# reflow.net
KiCad netlist of a schematic drawn in EAGLE
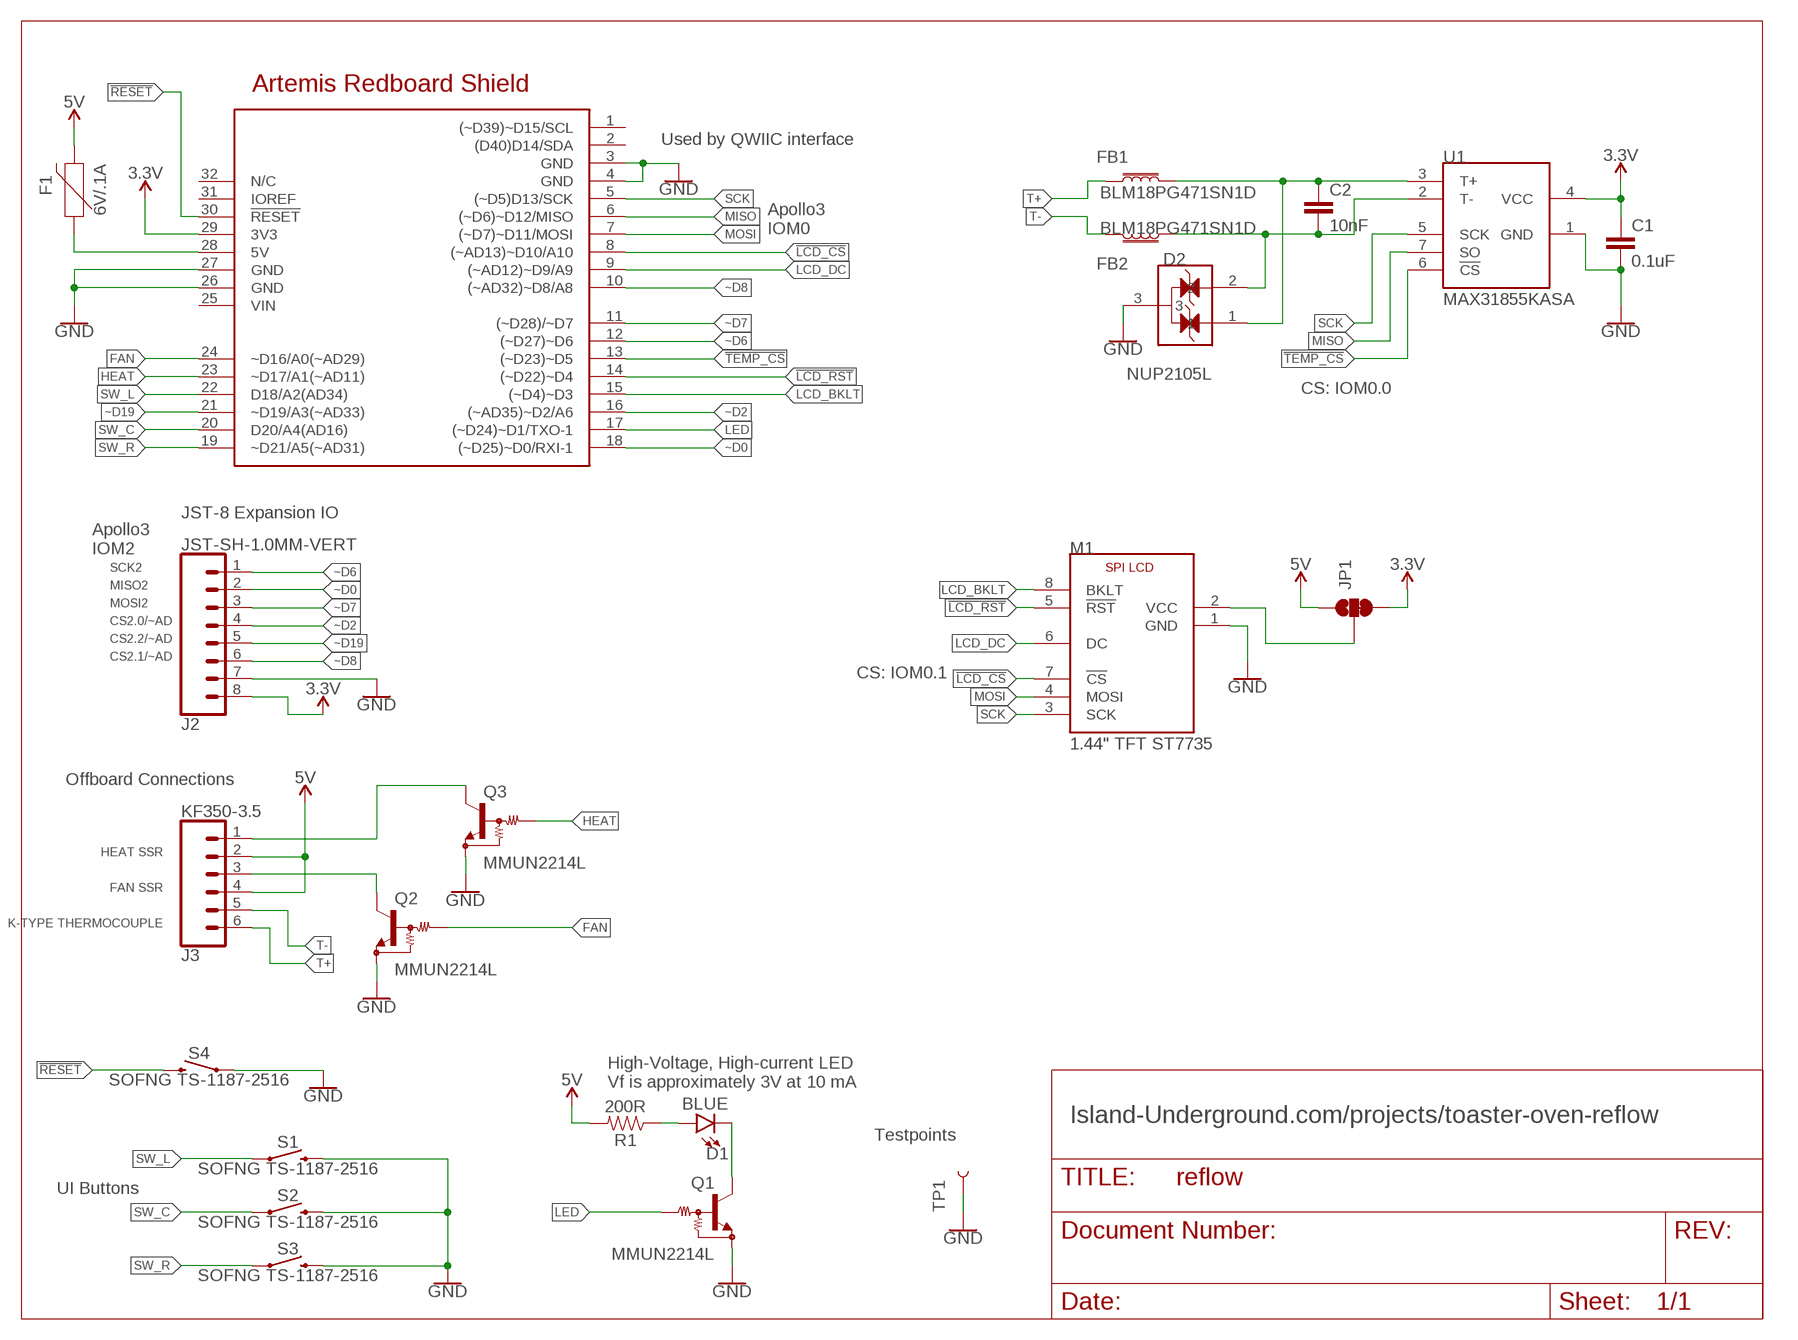
[diagram p0: schematic, sheet 1]

(export (version "E")
  (design (tool "Eeschema 10.0.6"))
  (components
    (comp (ref "C1")
      (value "0.1uF")
      (footprint "eagle-import:0603")
      (libsource (lib "eagle-import") (part "CAP-0603"))
    )
    (comp (ref "C2")
      (value "10nF")
      (footprint "eagle-import:0603")
      (libsource (lib "eagle-import") (part "CAP-0603"))
    )
    (comp (ref "D1")
      (value "BLUE")
      (footprint "eagle-import:LED-0603")
      (libsource (lib "eagle-import") (part "LED-BLUE0603"))
    )
    (comp (ref "D2")
      (value "NUP2105L")
      (footprint "eagle-import:SOT23")
      (libsource (lib "eagle-import") (part "NUP2105L-SOT23"))
    )
    (comp (ref "F1")
      (value "6V/.1A")
      (footprint "eagle-import:1206")
      (libsource (lib "eagle-import") (part "PPTC_0.75A"))
    )
    (comp (ref "FB1")
      (value "BLM18PG471SN1D")
      (footprint "eagle-import:0603")
      (libsource (lib "eagle-import") (part "FERRITE_BEAD-0603"))
    )
    (comp (ref "FB2")
      (value "BLM18PG471SN1D")
      (footprint "eagle-import:0603")
      (libsource (lib "eagle-import") (part "FERRITE_BEAD-0603"))
    )
    (comp (ref "J2")
      (value "JST-SH-1.0MM-VERT")
      (footprint "eagle-import:JST-SH-1.0MM-8V")
      (libsource (lib "eagle-import") (part "CON-1X8-JST-SH-1.0MM-VERT"))
    )
    (comp (ref "J3")
      (value "KF350-3.5")
      (footprint "eagle-import:SCREWTERMINAL-3.5MM-6")
      (libsource (lib "eagle-import") (part "CONN_063.5MM-6"))
    )
    (comp (ref "JP1")
      (value "JUMPER-SMT_3_1-NC_TRACE_SILK")
      (footprint "eagle-import:SMT-JUMPER_3_1-NC_TRACE_SILK")
      (libsource (lib "eagle-import") (part "JUMPER-SMT_3_1-NC_TRACE_SILK"))
    )
    (comp (ref "M1")
      (value "1.44\" TFT ST7735")
      (footprint "eagle-import:LCD-SPI-1P44")
      (libsource (lib "eagle-import") (part "SPI-LCD-1P44"))
    )
    (comp (ref "Q1")
      (value "MMUN2214L")
      (footprint "eagle-import:SOT23")
      (libsource (lib "eagle-import") (part "TRANSISTOR-NPN-PREBIASED-2R-SOT23"))
    )
    (comp (ref "Q2")
      (value "MMUN2214L")
      (footprint "eagle-import:SOT23")
      (libsource (lib "eagle-import") (part "TRANSISTOR-NPN-PREBIASED-2R-SOT23"))
    )
    (comp (ref "Q3")
      (value "MMUN2214L")
      (footprint "eagle-import:SOT23")
      (libsource (lib "eagle-import") (part "TRANSISTOR-NPN-PREBIASED-2R-SOT23"))
    )
    (comp (ref "R1")
      (value "200R")
      (footprint "eagle-import:0603")
      (libsource (lib "eagle-import") (part "RESISTOR0603"))
    )
    (comp (ref "S1")
      (value "SOFNG TS-1187-2516")
      (footprint "eagle-import:SWITCH-TAC-5.2")
      (libsource (lib "eagle-import") (part "SWITCH-TAC-5.2"))
    )
    (comp (ref "S2")
      (value "SOFNG TS-1187-2516")
      (footprint "eagle-import:SWITCH-TAC-5.2")
      (libsource (lib "eagle-import") (part "SWITCH-TAC-5.2"))
    )
    (comp (ref "S3")
      (value "SOFNG TS-1187-2516")
      (footprint "eagle-import:SWITCH-TAC-5.2")
      (libsource (lib "eagle-import") (part "SWITCH-TAC-5.2"))
    )
    (comp (ref "S4")
      (value "SOFNG TS-1187-2516")
      (footprint "eagle-import:SWITCH-TAC-5.2")
      (libsource (lib "eagle-import") (part "SWITCH-TAC-5.2"))
    )
    (comp (ref "TP1")
      (value "TESTPOINT-KEYSTONE-1035")
      (footprint "eagle-import:KEYSTONE-1035")
      (libsource (lib "eagle-import") (part "TESTPOINT-KEYSTONE-1035"))
    )
    (comp (ref "U$1")
      (value "ARTEMIS_REDBOARD_SHIELD")
      (footprint "eagle-import:ARTEMIS_REDBOARD_SHIELD")
      (libsource (lib "eagle-import") (part "ARTEMIS_REDBOARD_SHIELD"))
    )
    (comp (ref "U1")
      (value "MAX31855KASA")
      (footprint "eagle-import:SOIC-8")
      (libsource (lib "eagle-import") (part "MAX31855-SO8"))
    )
  )
  (nets
    (net (code "1") (name "/~{D0}") (class "Default")
      (node (ref "J2") (pin "2") (pinfunction "2_2") (pintype "passive"))
      (node (ref "U$1") (pin "18") (pinfunction "(~{D25})~{D0/RXI-1}_18") (pintype "bidirectional"))
    )
    (net (code "2") (name "/~{D2}") (class "Default")
      (node (ref "J2") (pin "4") (pinfunction "4_4") (pintype "passive"))
      (node (ref "U$1") (pin "16") (pinfunction "(~{AD35})~{D2/A6}_16") (pintype "bidirectional"))
    )
    (net (code "3") (name "/~{D6}") (class "Default")
      (node (ref "J2") (pin "1") (pinfunction "1_1") (pintype "passive"))
      (node (ref "U$1") (pin "12") (pinfunction "(~{D27})~{D6}_12") (pintype "bidirectional"))
    )
    (net (code "4") (name "/~{D7}") (class "Default")
      (node (ref "J2") (pin "3") (pinfunction "3_3") (pintype "passive"))
      (node (ref "U$1") (pin "11") (pinfunction "(~{D28})/~{D7}_11") (pintype "bidirectional"))
    )
    (net (code "5") (name "/~{D8}") (class "Default")
      (node (ref "J2") (pin "6") (pinfunction "6_6") (pintype "passive"))
      (node (ref "U$1") (pin "10") (pinfunction "(~{AD32})~{D8/A8}_10") (pintype "bidirectional"))
    )
    (net (code "6") (name "/~{D19}") (class "Default")
      (node (ref "J2") (pin "5") (pinfunction "5_5") (pintype "passive"))
      (node (ref "U$1") (pin "21") (pinfunction "~{D19/A3(}AD33)_21") (pintype "bidirectional"))
    )
    (net (code "7") (name "/~{LCD_CS}") (class "Default")
      (node (ref "M1") (pin "7") (pinfunction "~{CS}_7") (pintype "bidirectional"))
      (node (ref "U$1") (pin "8") (pinfunction "(~{AD13})~{D10/A10}_8") (pintype "bidirectional"))
    )
    (net (code "8") (name "/~{LCD_RST}") (class "Default")
      (node (ref "M1") (pin "5") (pinfunction "~{RST}_5") (pintype "bidirectional"))
      (node (ref "U$1") (pin "14") (pinfunction "(~{D22})~{D4}_14") (pintype "bidirectional"))
    )
    (net (code "9") (name "/~{RESET}") (class "Default")
      (node (ref "S4") (pin "2@1") (pinfunction "2_2@1") (pintype "passive"))
      (node (ref "S4") (pin "2@2") (pinfunction "2_2@2") (pintype "passive"))
      (node (ref "U$1") (pin "30") (pinfunction "~{RESET}_30") (pintype "bidirectional"))
    )
    (net (code "10") (name "/~{TEMP_CS}") (class "Default")
      (node (ref "U$1") (pin "13") (pinfunction "(~{D23})~{D5}_13") (pintype "bidirectional"))
      (node (ref "U1") (pin "6") (pinfunction "~{CS}_6") (pintype "bidirectional"))
    )
    (net (code "11") (name "3.3V") (class "Default")
      (node (ref "C1") (pin "1") (pinfunction "1_1") (pintype "passive"))
      (node (ref "J2") (pin "8") (pinfunction "8_8") (pintype "passive"))
      (node (ref "JP1") (pin "3") (pinfunction "3_3") (pintype "passive"))
      (node (ref "U$1") (pin "29") (pinfunction "3V3_29") (pintype "bidirectional"))
      (node (ref "U1") (pin "4") (pinfunction "VCC_4") (pintype "bidirectional"))
    )
    (net (code "12") (name "5V") (class "Default")
      (node (ref "F1") (pin "2") (pinfunction "2_2") (pintype "bidirectional"))
      (node (ref "J3") (pin "2") (pinfunction "2_2") (pintype "passive"))
      (node (ref "J3") (pin "4") (pinfunction "4_4") (pintype "passive"))
      (node (ref "JP1") (pin "1") (pinfunction "1_1") (pintype "passive"))
      (node (ref "R1") (pin "2") (pinfunction "2_2") (pintype "passive"))
    )
    (net (code "13") (name "FAN") (class "Default")
      (node (ref "Q2") (pin "1") (pinfunction "B_1") (pintype "passive"))
      (node (ref "U$1") (pin "24") (pinfunction "~{D16/A0(}AD29)_24") (pintype "bidirectional"))
    )
    (net (code "14") (name "GND") (class "Default")
      (node (ref "C1") (pin "2") (pinfunction "2_2") (pintype "passive"))
      (node (ref "D2") (pin "3") (pinfunction "3_3") (pintype "input"))
      (node (ref "J2") (pin "7") (pinfunction "7_7") (pintype "passive"))
      (node (ref "M1") (pin "1") (pinfunction "GND_1") (pintype "bidirectional"))
      (node (ref "Q1") (pin "2") (pinfunction "E_2") (pintype "passive"))
      (node (ref "Q2") (pin "2") (pinfunction "E_2") (pintype "passive"))
      (node (ref "Q3") (pin "2") (pinfunction "E_2") (pintype "passive"))
      (node (ref "S1") (pin "2@1") (pinfunction "2_2@1") (pintype "passive"))
      (node (ref "S1") (pin "2@2") (pinfunction "2_2@2") (pintype "passive"))
      (node (ref "S2") (pin "2@1") (pinfunction "2_2@1") (pintype "passive"))
      (node (ref "S2") (pin "2@2") (pinfunction "2_2@2") (pintype "passive"))
      (node (ref "S3") (pin "2@1") (pinfunction "2_2@1") (pintype "passive"))
      (node (ref "S3") (pin "2@2") (pinfunction "2_2@2") (pintype "passive"))
      (node (ref "S4") (pin "1@1") (pinfunction "1_1@1") (pintype "passive"))
      (node (ref "S4") (pin "1@2") (pinfunction "1_1@2") (pintype "passive"))
      (node (ref "TP1") (pin "P$1") (pinfunction "1_P$1") (pintype "bidirectional"))
      (node (ref "U$1") (pin "26") (pinfunction "GND_26") (pintype "bidirectional"))
      (node (ref "U$1") (pin "27") (pinfunction "GND_27") (pintype "bidirectional"))
      (node (ref "U$1") (pin "3") (pinfunction "GND_3") (pintype "bidirectional"))
      (node (ref "U$1") (pin "4") (pinfunction "GND_4") (pintype "bidirectional"))
      (node (ref "U1") (pin "1") (pinfunction "GND_1") (pintype "bidirectional"))
    )
    (net (code "15") (name "HEAT") (class "Default")
      (node (ref "Q3") (pin "1") (pinfunction "B_1") (pintype "passive"))
      (node (ref "U$1") (pin "23") (pinfunction "~{D17/A1(}AD11)_23") (pintype "bidirectional"))
    )
    (net (code "16") (name "LCD_BKLT") (class "Default")
      (node (ref "M1") (pin "8") (pinfunction "BKLT_8") (pintype "bidirectional"))
      (node (ref "U$1") (pin "15") (pinfunction "(~{D4})~{D3}_15") (pintype "bidirectional"))
    )
    (net (code "17") (name "LCD_DC") (class "Default")
      (node (ref "M1") (pin "6") (pinfunction "DC_6") (pintype "bidirectional"))
      (node (ref "U$1") (pin "9") (pinfunction "(~{AD12})~{D9/A9}_9") (pintype "bidirectional"))
    )
    (net (code "18") (name "LED") (class "Default")
      (node (ref "Q1") (pin "1") (pinfunction "B_1") (pintype "passive"))
      (node (ref "U$1") (pin "17") (pinfunction "(~{D24})~{D1/TXO-1}_17") (pintype "bidirectional"))
    )
    (net (code "19") (name "MISO") (class "Default")
      (node (ref "U$1") (pin "6") (pinfunction "(~{D6})~{D12/MISO}_6") (pintype "bidirectional"))
      (node (ref "U1") (pin "7") (pinfunction "SO_7") (pintype "bidirectional"))
    )
    (net (code "20") (name "MOSI") (class "Default")
      (node (ref "M1") (pin "4") (pinfunction "MOSI_4") (pintype "bidirectional"))
      (node (ref "U$1") (pin "7") (pinfunction "(~{D7})~{D11/MOSI}_7") (pintype "bidirectional"))
    )
    (net (code "21") (name "Net-(D1-PadA)") (class "Default")
      (node (ref "D1") (pin "A") (pinfunction "A_A") (pintype "passive"))
      (node (ref "R1") (pin "1") (pinfunction "1_1") (pintype "passive"))
    )
    (net (code "22") (name "Net-(M1-VCC)") (class "Default")
      (node (ref "JP1") (pin "2") (pinfunction "2_2") (pintype "passive"))
      (node (ref "M1") (pin "2") (pinfunction "VCC_2") (pintype "bidirectional"))
    )
    (net (code "23") (name "Net-(Q1-C)") (class "Default")
      (node (ref "D1") (pin "C") (pinfunction "C_C") (pintype "passive"))
      (node (ref "Q1") (pin "3") (pinfunction "C_3") (pintype "passive"))
    )
    (net (code "24") (name "Net-(Q2-C)") (class "Default")
      (node (ref "J3") (pin "3") (pinfunction "3_3") (pintype "passive"))
      (node (ref "Q2") (pin "3") (pinfunction "C_3") (pintype "passive"))
    )
    (net (code "25") (name "Net-(Q3-C)") (class "Default")
      (node (ref "J3") (pin "1") (pinfunction "1_1") (pintype "passive"))
      (node (ref "Q3") (pin "3") (pinfunction "C_3") (pintype "passive"))
    )
    (net (code "26") (name "Net-(U$1-5V)") (class "Default")
      (node (ref "F1") (pin "1") (pinfunction "1_1") (pintype "bidirectional"))
      (node (ref "U$1") (pin "28") (pinfunction "5V_28") (pintype "bidirectional"))
    )
    (net (code "27") (name "Net-(U1-T+)") (class "Default")
      (node (ref "C2") (pin "1") (pinfunction "1_1") (pintype "passive"))
      (node (ref "D2") (pin "1") (pinfunction "1_1") (pintype "input"))
      (node (ref "FB1") (pin "2") (pinfunction "2_2") (pintype "passive"))
      (node (ref "U1") (pin "3") (pinfunction "T+_3") (pintype "bidirectional"))
    )
    (net (code "28") (name "Net-(U1-T-)") (class "Default")
      (node (ref "C2") (pin "2") (pinfunction "2_2") (pintype "passive"))
      (node (ref "D2") (pin "2") (pinfunction "2_2") (pintype "input"))
      (node (ref "FB2") (pin "1") (pinfunction "1_1") (pintype "passive"))
      (node (ref "U1") (pin "2") (pinfunction "T-_2") (pintype "bidirectional"))
    )
    (net (code "29") (name "SCK") (class "Default")
      (node (ref "M1") (pin "3") (pinfunction "SCK_3") (pintype "bidirectional"))
      (node (ref "U$1") (pin "5") (pinfunction "(~{D5})D13/SCK_5") (pintype "bidirectional"))
      (node (ref "U1") (pin "5") (pinfunction "SCK_5") (pintype "bidirectional"))
    )
    (net (code "30") (name "SW_C") (class "Default")
      (node (ref "S2") (pin "1@1") (pinfunction "1_1@1") (pintype "passive"))
      (node (ref "S2") (pin "1@2") (pinfunction "1_1@2") (pintype "passive"))
      (node (ref "U$1") (pin "20") (pinfunction "D20/A4(AD16)_20") (pintype "bidirectional"))
    )
    (net (code "31") (name "SW_L") (class "Default")
      (node (ref "S1") (pin "1@1") (pinfunction "1_1@1") (pintype "passive"))
      (node (ref "S1") (pin "1@2") (pinfunction "1_1@2") (pintype "passive"))
      (node (ref "U$1") (pin "22") (pinfunction "D18/A2(AD34)_22") (pintype "bidirectional"))
    )
    (net (code "32") (name "SW_R") (class "Default")
      (node (ref "S3") (pin "1@1") (pinfunction "1_1@1") (pintype "passive"))
      (node (ref "S3") (pin "1@2") (pinfunction "1_1@2") (pintype "passive"))
      (node (ref "U$1") (pin "19") (pinfunction "~{D21/A5(}AD31)_19") (pintype "bidirectional"))
    )
    (net (code "33") (name "T+") (class "Default")
      (node (ref "FB1") (pin "1") (pinfunction "1_1") (pintype "passive"))
      (node (ref "J3") (pin "6") (pinfunction "6_6") (pintype "passive"))
    )
    (net (code "34") (name "T-") (class "Default")
      (node (ref "FB2") (pin "2") (pinfunction "2_2") (pintype "passive"))
      (node (ref "J3") (pin "5") (pinfunction "5_5") (pintype "passive"))
    )
    (net (code "35") (name "unconnected-(U$1-(D40)D14{slash}SDA-Pad2)") (class "Default")
      (node (ref "U$1") (pin "2") (pinfunction "(D40)D14/SDA_2") (pintype "bidirectional"))
    )
    (net (code "36") (name "unconnected-(U$1-(~{D39})~{D15{slash}SCL}-Pad1)") (class "Default")
      (node (ref "U$1") (pin "1") (pinfunction "(~{D39})~{D15/SCL}_1") (pintype "bidirectional"))
    )
    (net (code "37") (name "unconnected-(U$1-IOREF-Pad31)") (class "Default")
      (node (ref "U$1") (pin "31") (pinfunction "IOREF_31") (pintype "bidirectional"))
    )
    (net (code "38") (name "unconnected-(U$1-N{slash}C-Pad32)") (class "Default")
      (node (ref "U$1") (pin "32") (pinfunction "N/C_32") (pintype "no_connect"))
    )
    (net (code "39") (name "unconnected-(U$1-VIN-Pad25)") (class "Default")
      (node (ref "U$1") (pin "25") (pinfunction "VIN_25") (pintype "bidirectional"))
    )
  )
)
